# switcher_wifi.net
KiCad netlist of a schematic drawn in EAGLE
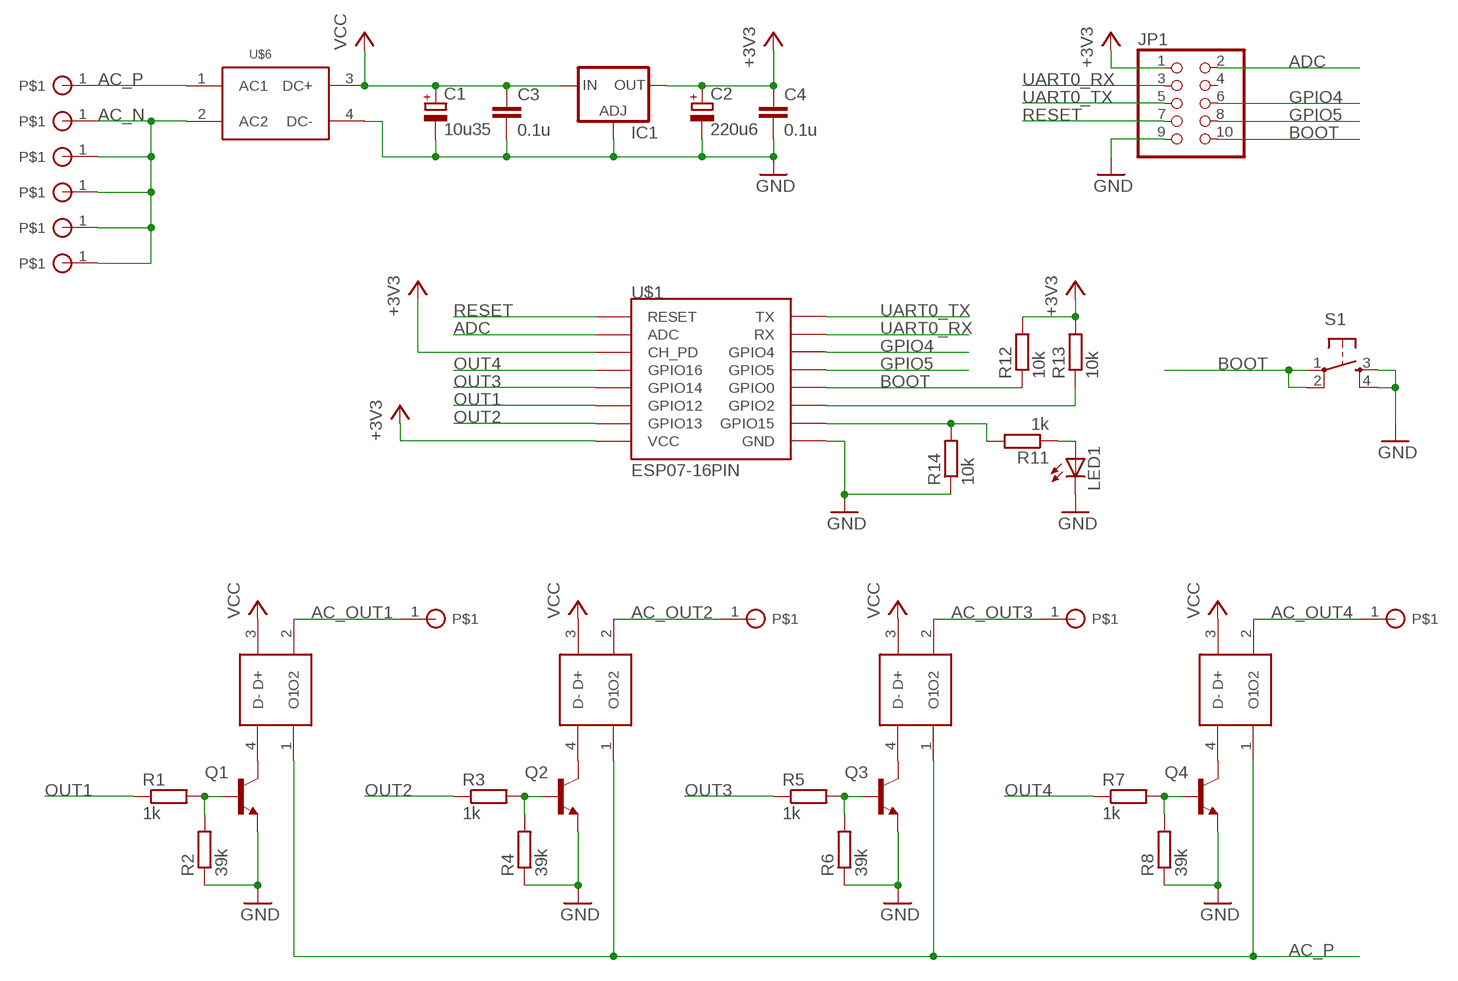
[diagram p0: schematic, sheet 1]

(export (version "E")
  (design (tool "Eeschema 10.0.6"))
  (components
    (comp (ref "C1")
      (value "10u35")
      (footprint "eagle-import:SMC_D")
      (libsource (lib "eagle-import") (part "CPOL-EUSMCD"))
    )
    (comp (ref "C2")
      (value "220u6")
      (footprint "eagle-import:SMC_D")
      (libsource (lib "eagle-import") (part "CPOL-EUSMCD"))
    )
    (comp (ref "C3")
      (value "0.1u")
      (footprint "eagle-import:C0805")
      (libsource (lib "eagle-import") (part "C-EUC0805"))
    )
    (comp (ref "C4")
      (value "0.1u")
      (footprint "eagle-import:C0805")
      (libsource (lib "eagle-import") (part "C-EUC0805"))
    )
    (comp (ref "IC1")
      (value "LD117ADT33TR")
      (footprint "eagle-import:DPACK")
      (libsource (lib "eagle-import") (part "LD117A?DT33TR"))
    )
    (comp (ref "JP1")
      (value "PINHD-2X5")
      (footprint "eagle-import:2X05")
      (libsource (lib "eagle-import") (part "PINHD-2X5"))
    )
    (comp (ref "LED1")
      (value "LED3MM")
      (footprint "eagle-import:LED3MM")
      (libsource (lib "eagle-import") (part "LED3MM"))
    )
    (comp (ref "Q1")
      (value "BC817-16SMD")
      (footprint "eagle-import:SOT23-BEC")
      (libsource (lib "eagle-import") (part "BC817SMD-16"))
    )
    (comp (ref "Q2")
      (value "BC817-16SMD")
      (footprint "eagle-import:SOT23-BEC")
      (libsource (lib "eagle-import") (part "BC817SMD-16"))
    )
    (comp (ref "Q3")
      (value "BC817-16SMD")
      (footprint "eagle-import:SOT23-BEC")
      (libsource (lib "eagle-import") (part "BC817SMD-16"))
    )
    (comp (ref "Q4")
      (value "BC817-16SMD")
      (footprint "eagle-import:SOT23-BEC")
      (libsource (lib "eagle-import") (part "BC817SMD-16"))
    )
    (comp (ref "R1")
      (value "1k")
      (footprint "eagle-import:M0805")
      (libsource (lib "eagle-import") (part "R-EU_M0805"))
    )
    (comp (ref "R2")
      (value "39k")
      (footprint "eagle-import:M0805")
      (libsource (lib "eagle-import") (part "R-EU_M0805"))
    )
    (comp (ref "R3")
      (value "1k")
      (footprint "eagle-import:M0805")
      (libsource (lib "eagle-import") (part "R-EU_M0805"))
    )
    (comp (ref "R4")
      (value "39k")
      (footprint "eagle-import:M0805")
      (libsource (lib "eagle-import") (part "R-EU_M0805"))
    )
    (comp (ref "R5")
      (value "1k")
      (footprint "eagle-import:M0805")
      (libsource (lib "eagle-import") (part "R-EU_M0805"))
    )
    (comp (ref "R6")
      (value "39k")
      (footprint "eagle-import:M0805")
      (libsource (lib "eagle-import") (part "R-EU_M0805"))
    )
    (comp (ref "R7")
      (value "1k")
      (footprint "eagle-import:M0805")
      (libsource (lib "eagle-import") (part "R-EU_M0805"))
    )
    (comp (ref "R8")
      (value "39k")
      (footprint "eagle-import:M0805")
      (libsource (lib "eagle-import") (part "R-EU_M0805"))
    )
    (comp (ref "R11")
      (value "1k")
      (footprint "eagle-import:M0805")
      (libsource (lib "eagle-import") (part "R-EU_M0805"))
    )
    (comp (ref "R12")
      (value "10k")
      (footprint "eagle-import:M0805")
      (libsource (lib "eagle-import") (part "R-EU_M0805"))
    )
    (comp (ref "R13")
      (value "10k")
      (footprint "eagle-import:M0805")
      (libsource (lib "eagle-import") (part "R-EU_M0805"))
    )
    (comp (ref "R14")
      (value "10k")
      (footprint "eagle-import:M0805")
      (libsource (lib "eagle-import") (part "R-EU_M0805"))
    )
    (comp (ref "S1")
      (value "TAC_SWITCHPTH")
      (footprint "eagle-import:TACTILE-PTH")
      (libsource (lib "eagle-import") (part "TAC_SWITCHPTH"))
    )
    (comp (ref "U$1")
      (value "ESP07-16PIN")
      (footprint "eagle-import:ESP07-16PIN")
      (libsource (lib "eagle-import") (part "ESP07-16PIN"))
    )
    (comp (ref "U$2")
      (value "G3MB-202P")
      (footprint "eagle-import:G3MB-202P")
      (libsource (lib "eagle-import") (part "G3MB-202P"))
    )
    (comp (ref "U$3")
      (value "G3MB-202P")
      (footprint "eagle-import:G3MB-202P")
      (libsource (lib "eagle-import") (part "G3MB-202P"))
    )
    (comp (ref "U$4")
      (value "G3MB-202P")
      (footprint "eagle-import:G3MB-202P")
      (libsource (lib "eagle-import") (part "G3MB-202P"))
    )
    (comp (ref "U$5")
      (value "G3MB-202P")
      (footprint "eagle-import:G3MB-202P")
      (libsource (lib "eagle-import") (part "G3MB-202P"))
    )
    (comp (ref "U$6")
      (value "AC-DC-5V-ALI1")
      (footprint "eagle-import:AC-DC-ALI1")
      (libsource (lib "eagle-import") (part "AC-DC-5V-ALI1"))
    )
    (comp (ref "U$8")
      (value "PWR_PIN")
      (footprint "eagle-import:PWR_PIN")
      (libsource (lib "eagle-import") (part "PWR_PIN"))
    )
    (comp (ref "U$9")
      (value "PWR_PIN")
      (footprint "eagle-import:PWR_PIN")
      (libsource (lib "eagle-import") (part "PWR_PIN"))
    )
    (comp (ref "U$10")
      (value "PWR_PIN")
      (footprint "eagle-import:PWR_PIN")
      (libsource (lib "eagle-import") (part "PWR_PIN"))
    )
    (comp (ref "U$11")
      (value "PWR_PIN")
      (footprint "eagle-import:PWR_PIN")
      (libsource (lib "eagle-import") (part "PWR_PIN"))
    )
    (comp (ref "U$12")
      (value "PWR_PIN")
      (footprint "eagle-import:PWR_PIN")
      (libsource (lib "eagle-import") (part "PWR_PIN"))
    )
    (comp (ref "U$13")
      (value "PWR_PIN")
      (footprint "eagle-import:PWR_PIN")
      (libsource (lib "eagle-import") (part "PWR_PIN"))
    )
    (comp (ref "U$14")
      (value "PWR_PIN")
      (footprint "eagle-import:PWR_PIN")
      (libsource (lib "eagle-import") (part "PWR_PIN"))
    )
    (comp (ref "U$15")
      (value "PWR_PIN")
      (footprint "eagle-import:PWR_PIN")
      (libsource (lib "eagle-import") (part "PWR_PIN"))
    )
    (comp (ref "U$16")
      (value "PWR_PIN")
      (footprint "eagle-import:PWR_PIN")
      (libsource (lib "eagle-import") (part "PWR_PIN"))
    )
    (comp (ref "U$17")
      (value "PWR_PIN")
      (footprint "eagle-import:PWR_PIN")
      (libsource (lib "eagle-import") (part "PWR_PIN"))
    )
  )
  (nets
    (net (code "1") (name "+3V3") (class "Default")
      (node (ref "C2") (pin "+") (pinfunction "+_+") (pintype "passive"))
      (node (ref "C4") (pin "1") (pinfunction "1_1") (pintype "passive"))
      (node (ref "IC1") (pin "4") (pinfunction "OUT_4") (pintype "passive"))
      (node (ref "JP1") (pin "1") (pinfunction "1_1") (pintype "passive"))
      (node (ref "R12") (pin "2") (pinfunction "2_2") (pintype "passive"))
      (node (ref "R13") (pin "2") (pinfunction "2_2") (pintype "passive"))
      (node (ref "U$1") (pin "CH_PD") (pinfunction "CH_PD_CH_PD") (pintype "bidirectional"))
      (node (ref "U$1") (pin "VCC") (pinfunction "VCC_VCC") (pintype "bidirectional"))
    )
    (net (code "2") (name "/AC_N") (class "Default")
      (node (ref "U$14") (pin "1") (pinfunction "P$1_1") (pintype "bidirectional"))
      (node (ref "U$15") (pin "1") (pinfunction "P$1_1") (pintype "bidirectional"))
      (node (ref "U$16") (pin "1") (pinfunction "P$1_1") (pintype "bidirectional"))
      (node (ref "U$17") (pin "1") (pinfunction "P$1_1") (pintype "bidirectional"))
      (node (ref "U$6") (pin "2") (pinfunction "AC2_2") (pintype "bidirectional"))
      (node (ref "U$9") (pin "1") (pinfunction "P$1_1") (pintype "bidirectional"))
    )
    (net (code "3") (name "/AC_OUT1") (class "Default")
      (node (ref "U$10") (pin "1") (pinfunction "P$1_1") (pintype "bidirectional"))
      (node (ref "U$2") (pin "2") (pinfunction "O2_2") (pintype "bidirectional"))
    )
    (net (code "4") (name "/AC_OUT2") (class "Default")
      (node (ref "U$11") (pin "1") (pinfunction "P$1_1") (pintype "bidirectional"))
      (node (ref "U$3") (pin "2") (pinfunction "O2_2") (pintype "bidirectional"))
    )
    (net (code "5") (name "/AC_OUT3") (class "Default")
      (node (ref "U$12") (pin "1") (pinfunction "P$1_1") (pintype "bidirectional"))
      (node (ref "U$4") (pin "2") (pinfunction "O2_2") (pintype "bidirectional"))
    )
    (net (code "6") (name "/AC_OUT4") (class "Default")
      (node (ref "U$13") (pin "1") (pinfunction "P$1_1") (pintype "bidirectional"))
      (node (ref "U$5") (pin "2") (pinfunction "O2_2") (pintype "bidirectional"))
    )
    (net (code "7") (name "/AC_P") (class "Default")
      (node (ref "U$2") (pin "1") (pinfunction "O1_1") (pintype "bidirectional"))
      (node (ref "U$3") (pin "1") (pinfunction "O1_1") (pintype "bidirectional"))
      (node (ref "U$4") (pin "1") (pinfunction "O1_1") (pintype "bidirectional"))
      (node (ref "U$5") (pin "1") (pinfunction "O1_1") (pintype "bidirectional"))
      (node (ref "U$6") (pin "1") (pinfunction "AC1_1") (pintype "bidirectional"))
      (node (ref "U$8") (pin "1") (pinfunction "P$1_1") (pintype "bidirectional"))
    )
    (net (code "8") (name "/ADC") (class "Default")
      (node (ref "JP1") (pin "2") (pinfunction "2_2") (pintype "passive"))
      (node (ref "U$1") (pin "ADC") (pinfunction "ADC_ADC") (pintype "bidirectional"))
    )
    (net (code "9") (name "/BOOT") (class "Default")
      (node (ref "JP1") (pin "10") (pinfunction "10_10") (pintype "passive"))
      (node (ref "R12") (pin "1") (pinfunction "1_1") (pintype "passive"))
      (node (ref "S1") (pin "1") (pinfunction "1_1") (pintype "passive"))
      (node (ref "S1") (pin "2") (pinfunction "2_2") (pintype "passive"))
      (node (ref "U$1") (pin "GPIO0") (pinfunction "GPIO0_GPIO0") (pintype "bidirectional"))
    )
    (net (code "10") (name "/GPIO4") (class "Default")
      (node (ref "JP1") (pin "6") (pinfunction "6_6") (pintype "passive"))
      (node (ref "U$1") (pin "GPIO4") (pinfunction "GPIO4_GPIO4") (pintype "bidirectional"))
    )
    (net (code "11") (name "/GPIO5") (class "Default")
      (node (ref "JP1") (pin "8") (pinfunction "8_8") (pintype "passive"))
      (node (ref "U$1") (pin "GPIO5") (pinfunction "GPIO5_GPIO5") (pintype "bidirectional"))
    )
    (net (code "12") (name "/OUT1") (class "Default")
      (node (ref "R1") (pin "1") (pinfunction "1_1") (pintype "passive"))
      (node (ref "U$1") (pin "GPIO12") (pinfunction "GPIO12_GPIO12") (pintype "bidirectional"))
    )
    (net (code "13") (name "/OUT2") (class "Default")
      (node (ref "R3") (pin "1") (pinfunction "1_1") (pintype "passive"))
      (node (ref "U$1") (pin "GPIO13") (pinfunction "GPIO13_GPIO13") (pintype "bidirectional"))
    )
    (net (code "14") (name "/OUT3") (class "Default")
      (node (ref "R5") (pin "1") (pinfunction "1_1") (pintype "passive"))
      (node (ref "U$1") (pin "GPIO14") (pinfunction "GPIO14_GPIO14") (pintype "bidirectional"))
    )
    (net (code "15") (name "/OUT4") (class "Default")
      (node (ref "R7") (pin "1") (pinfunction "1_1") (pintype "passive"))
      (node (ref "U$1") (pin "GPIO16") (pinfunction "GPIO16_GPIO16") (pintype "bidirectional"))
    )
    (net (code "16") (name "/RESET") (class "Default")
      (node (ref "JP1") (pin "7") (pinfunction "7_7") (pintype "passive"))
      (node (ref "U$1") (pin "REST") (pinfunction "RESET_REST") (pintype "bidirectional"))
    )
    (net (code "17") (name "/UART0_RX") (class "Default")
      (node (ref "JP1") (pin "3") (pinfunction "3_3") (pintype "passive"))
      (node (ref "U$1") (pin "RX") (pinfunction "RX_RX") (pintype "bidirectional"))
    )
    (net (code "18") (name "/UART0_TX") (class "Default")
      (node (ref "JP1") (pin "5") (pinfunction "5_5") (pintype "passive"))
      (node (ref "U$1") (pin "TX") (pinfunction "TX_TX") (pintype "bidirectional"))
    )
    (net (code "19") (name "GND") (class "Default")
      (node (ref "C1") (pin "-") (pinfunction "-_-") (pintype "passive"))
      (node (ref "C2") (pin "-") (pinfunction "-_-") (pintype "passive"))
      (node (ref "C3") (pin "2") (pinfunction "2_2") (pintype "passive"))
      (node (ref "C4") (pin "2") (pinfunction "2_2") (pintype "passive"))
      (node (ref "IC1") (pin "1") (pinfunction "ADJ_1") (pintype "input"))
      (node (ref "JP1") (pin "9") (pinfunction "9_9") (pintype "passive"))
      (node (ref "LED1") (pin "K") (pinfunction "C_K") (pintype "passive"))
      (node (ref "Q1") (pin "E") (pinfunction "E_E") (pintype "passive"))
      (node (ref "Q2") (pin "E") (pinfunction "E_E") (pintype "passive"))
      (node (ref "Q3") (pin "E") (pinfunction "E_E") (pintype "passive"))
      (node (ref "Q4") (pin "E") (pinfunction "E_E") (pintype "passive"))
      (node (ref "R14") (pin "1") (pinfunction "1_1") (pintype "passive"))
      (node (ref "R2") (pin "1") (pinfunction "1_1") (pintype "passive"))
      (node (ref "R4") (pin "1") (pinfunction "1_1") (pintype "passive"))
      (node (ref "R6") (pin "1") (pinfunction "1_1") (pintype "passive"))
      (node (ref "R8") (pin "1") (pinfunction "1_1") (pintype "passive"))
      (node (ref "S1") (pin "3") (pinfunction "3_3") (pintype "passive"))
      (node (ref "S1") (pin "4") (pinfunction "4_4") (pintype "passive"))
      (node (ref "U$1") (pin "GND") (pinfunction "GND_GND") (pintype "bidirectional"))
      (node (ref "U$6") (pin "4") (pinfunction "DC-_4") (pintype "bidirectional"))
    )
    (net (code "20") (name "Net-(LED1-PadA)") (class "Default")
      (node (ref "LED1") (pin "A") (pinfunction "A_A") (pintype "passive"))
      (node (ref "R11") (pin "1") (pinfunction "1_1") (pintype "passive"))
    )
    (net (code "21") (name "Net-(Q1-PadB)") (class "Default")
      (node (ref "Q1") (pin "B") (pinfunction "B_B") (pintype "passive"))
      (node (ref "R1") (pin "2") (pinfunction "2_2") (pintype "passive"))
      (node (ref "R2") (pin "2") (pinfunction "2_2") (pintype "passive"))
    )
    (net (code "22") (name "Net-(Q2-PadB)") (class "Default")
      (node (ref "Q2") (pin "B") (pinfunction "B_B") (pintype "passive"))
      (node (ref "R3") (pin "2") (pinfunction "2_2") (pintype "passive"))
      (node (ref "R4") (pin "2") (pinfunction "2_2") (pintype "passive"))
    )
    (net (code "23") (name "Net-(Q3-PadB)") (class "Default")
      (node (ref "Q3") (pin "B") (pinfunction "B_B") (pintype "passive"))
      (node (ref "R5") (pin "2") (pinfunction "2_2") (pintype "passive"))
      (node (ref "R6") (pin "2") (pinfunction "2_2") (pintype "passive"))
    )
    (net (code "24") (name "Net-(Q4-PadB)") (class "Default")
      (node (ref "Q4") (pin "B") (pinfunction "B_B") (pintype "passive"))
      (node (ref "R7") (pin "2") (pinfunction "2_2") (pintype "passive"))
      (node (ref "R8") (pin "2") (pinfunction "2_2") (pintype "passive"))
    )
    (net (code "25") (name "Net-(R11-Pad2)") (class "Default")
      (node (ref "R11") (pin "2") (pinfunction "2_2") (pintype "passive"))
      (node (ref "R14") (pin "2") (pinfunction "2_2") (pintype "passive"))
      (node (ref "U$1") (pin "GPIO15") (pinfunction "GPIO15_GPIO15") (pintype "bidirectional"))
    )
    (net (code "26") (name "Net-(R13-Pad1)") (class "Default")
      (node (ref "R13") (pin "1") (pinfunction "1_1") (pintype "passive"))
      (node (ref "U$1") (pin "GPIO2") (pinfunction "GPIO2_GPIO2") (pintype "bidirectional"))
    )
    (net (code "27") (name "Net-(U$2-D-)") (class "Default")
      (node (ref "Q1") (pin "C") (pinfunction "C_C") (pintype "passive"))
      (node (ref "U$2") (pin "4") (pinfunction "D-_4") (pintype "bidirectional"))
    )
    (net (code "28") (name "Net-(U$3-D-)") (class "Default")
      (node (ref "Q2") (pin "C") (pinfunction "C_C") (pintype "passive"))
      (node (ref "U$3") (pin "4") (pinfunction "D-_4") (pintype "bidirectional"))
    )
    (net (code "29") (name "Net-(U$4-D-)") (class "Default")
      (node (ref "Q3") (pin "C") (pinfunction "C_C") (pintype "passive"))
      (node (ref "U$4") (pin "4") (pinfunction "D-_4") (pintype "bidirectional"))
    )
    (net (code "30") (name "Net-(U$5-D-)") (class "Default")
      (node (ref "Q4") (pin "C") (pinfunction "C_C") (pintype "passive"))
      (node (ref "U$5") (pin "4") (pinfunction "D-_4") (pintype "bidirectional"))
    )
    (net (code "31") (name "VCC") (class "Default")
      (node (ref "C1") (pin "+") (pinfunction "+_+") (pintype "passive"))
      (node (ref "C3") (pin "1") (pinfunction "1_1") (pintype "passive"))
      (node (ref "IC1") (pin "3") (pinfunction "IN_3") (pintype "input"))
      (node (ref "U$2") (pin "3") (pinfunction "D+_3") (pintype "bidirectional"))
      (node (ref "U$3") (pin "3") (pinfunction "D+_3") (pintype "bidirectional"))
      (node (ref "U$4") (pin "3") (pinfunction "D+_3") (pintype "bidirectional"))
      (node (ref "U$5") (pin "3") (pinfunction "D+_3") (pintype "bidirectional"))
      (node (ref "U$6") (pin "3") (pinfunction "DC+_3") (pintype "bidirectional"))
    )
    (net (code "32") (name "unconnected-(JP1-Pad4)") (class "Default")
      (node (ref "JP1") (pin "4") (pinfunction "4_4") (pintype "passive"))
    )
  )
)
